# esp.net
KiCad netlist of a schematic drawn in EAGLE
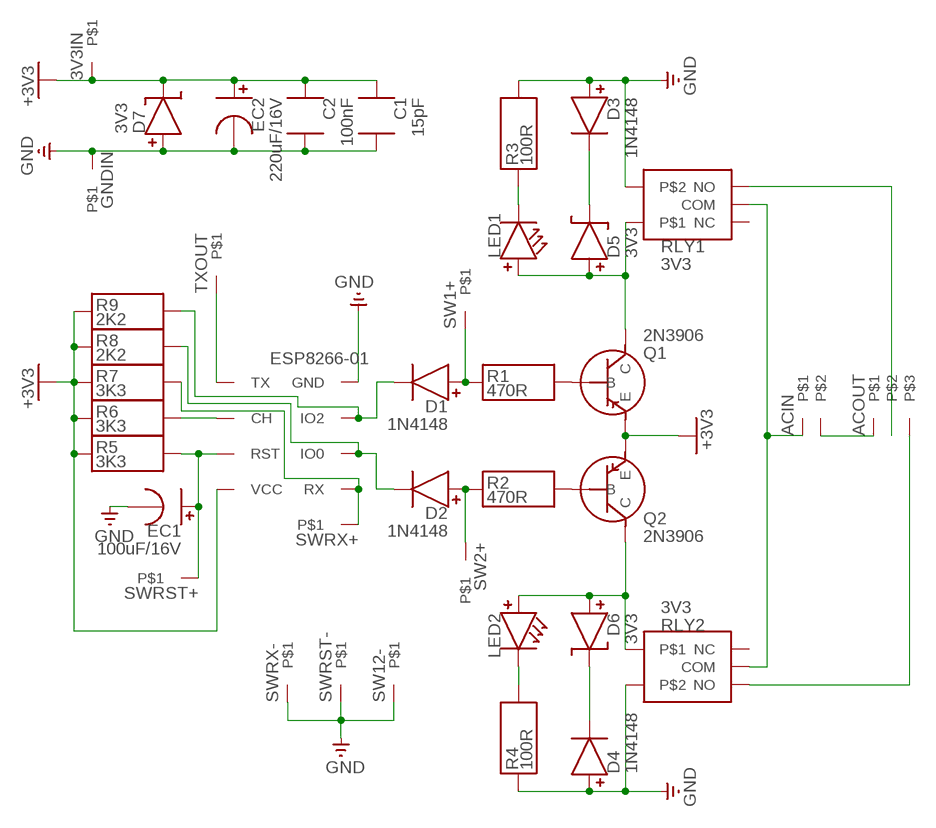
[diagram p0: schematic, sheet 1]

(export (version "E")
  (design (tool "Eeschema 10.0.6"))
  (components
    (comp (ref "3V3IN")
      (value "CON1PINPLUG1")
      (footprint "eagle-import:PINPLUG1")
      (libsource (lib "eagle-import") (part "CON1PINPLUG1"))
    )
    (comp (ref "ACIN")
      (value "CON2CON5.0S2T")
      (footprint "eagle-import:CON5.0S2T")
      (libsource (lib "eagle-import") (part "CON2CON5.0S2T"))
    )
    (comp (ref "ACOUT")
      (value "CON3CON5.0S3T")
      (footprint "eagle-import:CON5.0S3T")
      (libsource (lib "eagle-import") (part "CON3CON5.0S3T"))
    )
    (comp (ref "C1")
      (value "15pF")
      (footprint "eagle-import:CERCAP3.2S")
      (libsource (lib "eagle-import") (part "CAPACITORCERCAP3.2S"))
    )
    (comp (ref "C2")
      (value "100nF")
      (footprint "eagle-import:CERCAP5.6S")
      (libsource (lib "eagle-import") (part "CAPACITORCERCAP5.6S"))
    )
    (comp (ref "D1")
      (value "1N4148")
      (footprint "eagle-import:RD5.0S1.8D")
      (libsource (lib "eagle-import") (part "RECTDIODERD5.0S1.8D"))
    )
    (comp (ref "D2")
      (value "1N4148")
      (footprint "eagle-import:RD5.0S1.8D")
      (libsource (lib "eagle-import") (part "RECTDIODERD5.0S1.8D"))
    )
    (comp (ref "D3")
      (value "1N4148")
      (footprint "eagle-import:RD5.0S1.8D")
      (libsource (lib "eagle-import") (part "RECTDIODERD5.0S1.8D"))
    )
    (comp (ref "D4")
      (value "1N4148")
      (footprint "eagle-import:RD5.0S1.8D")
      (libsource (lib "eagle-import") (part "RECTDIODERD5.0S1.8D"))
    )
    (comp (ref "D5")
      (value "3V3")
      (footprint "eagle-import:ZD6.0S2.0D")
      (libsource (lib "eagle-import") (part "ZENDIODEZD6.0S2.0D"))
    )
    (comp (ref "D6")
      (value "3V3")
      (footprint "eagle-import:ZD6.0S2.0D")
      (libsource (lib "eagle-import") (part "ZENDIODEZD6.0S2.0D"))
    )
    (comp (ref "D7")
      (value "3V3")
      (footprint "eagle-import:ZD6.0S2.0D")
      (libsource (lib "eagle-import") (part "ZENDIODEZD6.0S2.0D"))
    )
    (comp (ref "EC1")
      (value "100uF/16V")
      (footprint "eagle-import:ECAP3.2S5.0D")
      (libsource (lib "eagle-import") (part "ECAPACITORECAP3.2S5.0D"))
    )
    (comp (ref "EC2")
      (value "220uF/16V")
      (footprint "eagle-import:ECAP3.2S5.0D")
      (libsource (lib "eagle-import") (part "ECAPACITORECAP3.2S5.0D"))
    )
    (comp (ref "ESP8266-01")
      (value "ESP8266E01ESP8266E01")
      (footprint "eagle-import:ESP8266E01")
      (libsource (lib "eagle-import") (part "ESP8266E01ESP8266E01"))
    )
    (comp (ref "GNDIN")
      (value "CON1PINPLUG1")
      (footprint "eagle-import:PINPLUG1")
      (libsource (lib "eagle-import") (part "CON1PINPLUG1"))
    )
    (comp (ref "LED1")
      (value "LEDLED3.2S5.0D")
      (footprint "eagle-import:LED3.2S5.0D")
      (libsource (lib "eagle-import") (part "LEDLED3.2S5.0D"))
    )
    (comp (ref "LED2")
      (value "LEDLED3.2S5.0D")
      (footprint "eagle-import:LED3.2S5.0D")
      (libsource (lib "eagle-import") (part "LEDLED3.2S5.0D"))
    )
    (comp (ref "Q1")
      (value "2N3906")
      (footprint "eagle-import:TO92")
      (libsource (lib "eagle-import") (part "BJTPNPTO92"))
    )
    (comp (ref "Q2")
      (value "2N3906")
      (footprint "eagle-import:TO92")
      (libsource (lib "eagle-import") (part "BJTPNPTO92"))
    )
    (comp (ref "R1")
      (value "470R")
      (footprint "eagle-import:HOR.25W")
      (libsource (lib "eagle-import") (part "RESISTORHOR.25W"))
    )
    (comp (ref "R2")
      (value "470R")
      (footprint "eagle-import:HOR.25W")
      (libsource (lib "eagle-import") (part "RESISTORHOR.25W"))
    )
    (comp (ref "R3")
      (value "100R")
      (footprint "eagle-import:HOR.25W")
      (libsource (lib "eagle-import") (part "RESISTORHOR.25W"))
    )
    (comp (ref "R4")
      (value "100R")
      (footprint "eagle-import:HOR.25W")
      (libsource (lib "eagle-import") (part "RESISTORHOR.25W"))
    )
    (comp (ref "R5")
      (value "3K3")
      (footprint "eagle-import:HOR.25W")
      (libsource (lib "eagle-import") (part "RESISTORHOR.25W"))
    )
    (comp (ref "R6")
      (value "3K3")
      (footprint "eagle-import:HOR.25W")
      (libsource (lib "eagle-import") (part "RESISTORHOR.25W"))
    )
    (comp (ref "R7")
      (value "3K3")
      (footprint "eagle-import:HOR.25W")
      (libsource (lib "eagle-import") (part "RESISTORHOR.25W"))
    )
    (comp (ref "R8")
      (value "2K2")
      (footprint "eagle-import:HOR.25W")
      (libsource (lib "eagle-import") (part "RESISTORHOR.25W"))
    )
    (comp (ref "R9")
      (value "2K2")
      (footprint "eagle-import:HOR.25W")
      (libsource (lib "eagle-import") (part "RESISTORHOR.25W"))
    )
    (comp (ref "RLY1")
      (value "3V3")
      (footprint "eagle-import:RLY15W19L")
      (libsource (lib "eagle-import") (part "RELAY5RLY15W19L"))
    )
    (comp (ref "RLY2")
      (value "3V3")
      (footprint "eagle-import:RLY15W19L")
      (libsource (lib "eagle-import") (part "RELAY5RLY15W19L"))
    )
    (comp (ref "SW1+")
      (value "CON1PINPLUG1")
      (footprint "eagle-import:PINPLUG1")
      (libsource (lib "eagle-import") (part "CON1PINPLUG1"))
    )
    (comp (ref "SW2+")
      (value "CON1PINPLUG1")
      (footprint "eagle-import:PINPLUG1")
      (libsource (lib "eagle-import") (part "CON1PINPLUG1"))
    )
    (comp (ref "SW12-")
      (value "CON1PINPLUG1")
      (footprint "eagle-import:PINPLUG1")
      (libsource (lib "eagle-import") (part "CON1PINPLUG1"))
    )
    (comp (ref "SWRST+")
      (value "CON1PINPLUG1")
      (footprint "eagle-import:PINPLUG1")
      (libsource (lib "eagle-import") (part "CON1PINPLUG1"))
    )
    (comp (ref "SWRST-")
      (value "CON1PINPLUG1")
      (footprint "eagle-import:PINPLUG1")
      (libsource (lib "eagle-import") (part "CON1PINPLUG1"))
    )
    (comp (ref "SWRX+")
      (value "CON1PINPLUG1")
      (footprint "eagle-import:PINPLUG1")
      (libsource (lib "eagle-import") (part "CON1PINPLUG1"))
    )
    (comp (ref "SWRX-")
      (value "CON1PINPLUG1")
      (footprint "eagle-import:PINPLUG1")
      (libsource (lib "eagle-import") (part "CON1PINPLUG1"))
    )
    (comp (ref "TXOUT")
      (value "CON1PINPLUG1")
      (footprint "eagle-import:PINPLUG1")
      (libsource (lib "eagle-import") (part "CON1PINPLUG1"))
    )
  )
  (nets
    (net (code "1") (name "+3V3") (class "Default")
      (node (ref "3V3IN") (pin "P$1") (pinfunction "P$1_P$1") (pintype "bidirectional"))
      (node (ref "C1") (pin "P$1") (pinfunction "P$1_P$1") (pintype "passive"))
      (node (ref "C2") (pin "P$1") (pinfunction "P$1_P$1") (pintype "passive"))
      (node (ref "D7") (pin "P-") (pinfunction "P-_P-") (pintype "passive"))
      (node (ref "EC2") (pin "P+") (pinfunction "P+_P+") (pintype "passive"))
      (node (ref "ESP8266-01") (pin "VCC") (pinfunction "VCC_VCC") (pintype "bidirectional"))
      (node (ref "Q1") (pin "3") (pinfunction "E_3") (pintype "bidirectional"))
      (node (ref "Q2") (pin "3") (pinfunction "E_3") (pintype "bidirectional"))
      (node (ref "R5") (pin "P$1") (pinfunction "P$1_P$1") (pintype "passive"))
      (node (ref "R6") (pin "P$1") (pinfunction "P$1_P$1") (pintype "passive"))
      (node (ref "R7") (pin "P$1") (pinfunction "P$1_P$1") (pintype "passive"))
      (node (ref "R8") (pin "P$1") (pinfunction "P$1_P$1") (pintype "passive"))
      (node (ref "R9") (pin "P$1") (pinfunction "P$1_P$1") (pintype "passive"))
    )
    (net (code "2") (name "GND") (class "Default")
      (node (ref "C1") (pin "P$2") (pinfunction "P$2_P$2") (pintype "passive"))
      (node (ref "C2") (pin "P$2") (pinfunction "P$2_P$2") (pintype "passive"))
      (node (ref "D3") (pin "P+") (pinfunction "P+_P+") (pintype "passive"))
      (node (ref "D4") (pin "P+") (pinfunction "P+_P+") (pintype "passive"))
      (node (ref "D7") (pin "P+") (pinfunction "P+_P+") (pintype "passive"))
      (node (ref "EC1") (pin "P-") (pinfunction "P-_P-") (pintype "passive"))
      (node (ref "EC2") (pin "P-") (pinfunction "P-_P-") (pintype "passive"))
      (node (ref "ESP8266-01") (pin "GND") (pinfunction "GND_GND") (pintype "bidirectional"))
      (node (ref "GNDIN") (pin "P$1") (pinfunction "P$1_P$1") (pintype "bidirectional"))
      (node (ref "R3") (pin "P$2") (pinfunction "P$2_P$2") (pintype "passive"))
      (node (ref "R4") (pin "P$1") (pinfunction "P$1_P$1") (pintype "passive"))
      (node (ref "RLY1") (pin "P$2") (pinfunction "P$2_P$2") (pintype "passive"))
      (node (ref "RLY2") (pin "P$2") (pinfunction "P$2_P$2") (pintype "passive"))
      (node (ref "SW12-") (pin "P$1") (pinfunction "P$1_P$1") (pintype "bidirectional"))
      (node (ref "SWRST-") (pin "P$1") (pinfunction "P$1_P$1") (pintype "bidirectional"))
      (node (ref "SWRX-") (pin "P$1") (pinfunction "P$1_P$1") (pintype "bidirectional"))
    )
    (net (code "3") (name "Net-(ACIN-PadP$1)") (class "Default")
      (node (ref "ACIN") (pin "P$1") (pinfunction "P$1_P$1") (pintype "bidirectional"))
      (node (ref "RLY1") (pin "COM") (pinfunction "COM_COM") (pintype "bidirectional"))
      (node (ref "RLY2") (pin "COM") (pinfunction "COM_COM") (pintype "bidirectional"))
    )
    (net (code "4") (name "Net-(ACIN-PadP$2)") (class "Default")
      (node (ref "ACIN") (pin "P$2") (pinfunction "P$2_P$2") (pintype "bidirectional"))
      (node (ref "ACOUT") (pin "P$1") (pinfunction "P$1_P$1") (pintype "bidirectional"))
    )
    (net (code "5") (name "Net-(ACOUT-PadP$2)") (class "Default")
      (node (ref "ACOUT") (pin "P$2") (pinfunction "P$2_P$2") (pintype "bidirectional"))
      (node (ref "RLY1") (pin "NO") (pinfunction "NO_NO") (pintype "bidirectional"))
    )
    (net (code "6") (name "Net-(ACOUT-PadP$3)") (class "Default")
      (node (ref "ACOUT") (pin "P$3") (pinfunction "P$3_P$3") (pintype "bidirectional"))
      (node (ref "RLY2") (pin "NO") (pinfunction "NO_NO") (pintype "bidirectional"))
    )
    (net (code "7") (name "Net-(D1-PadP+)") (class "Default")
      (node (ref "D1") (pin "P+") (pinfunction "P+_P+") (pintype "passive"))
      (node (ref "R1") (pin "P$1") (pinfunction "P$1_P$1") (pintype "passive"))
      (node (ref "SW1+") (pin "P$1") (pinfunction "P$1_P$1") (pintype "bidirectional"))
    )
    (net (code "8") (name "Net-(D1-PadP-)") (class "Default")
      (node (ref "D1") (pin "P-") (pinfunction "P-_P-") (pintype "passive"))
      (node (ref "ESP8266-01") (pin "IO2") (pinfunction "IO2_IO2") (pintype "bidirectional"))
      (node (ref "R9") (pin "P$2") (pinfunction "P$2_P$2") (pintype "passive"))
    )
    (net (code "9") (name "Net-(D2-PadP+)") (class "Default")
      (node (ref "D2") (pin "P+") (pinfunction "P+_P+") (pintype "passive"))
      (node (ref "R2") (pin "P$1") (pinfunction "P$1_P$1") (pintype "passive"))
      (node (ref "SW2+") (pin "P$1") (pinfunction "P$1_P$1") (pintype "bidirectional"))
    )
    (net (code "10") (name "Net-(D2-PadP-)") (class "Default")
      (node (ref "D2") (pin "P-") (pinfunction "P-_P-") (pintype "passive"))
      (node (ref "ESP8266-01") (pin "IO0") (pinfunction "IO0_IO0") (pintype "bidirectional"))
      (node (ref "R8") (pin "P$2") (pinfunction "P$2_P$2") (pintype "passive"))
    )
    (net (code "11") (name "Net-(D3-PadP-)") (class "Default")
      (node (ref "D3") (pin "P-") (pinfunction "P-_P-") (pintype "passive"))
      (node (ref "D5") (pin "P-") (pinfunction "P-_P-") (pintype "passive"))
    )
    (net (code "12") (name "Net-(D4-PadP-)") (class "Default")
      (node (ref "D4") (pin "P-") (pinfunction "P-_P-") (pintype "passive"))
      (node (ref "D6") (pin "P-") (pinfunction "P-_P-") (pintype "passive"))
    )
    (net (code "13") (name "Net-(EC1-PadP+)") (class "Default")
      (node (ref "EC1") (pin "P+") (pinfunction "P+_P+") (pintype "passive"))
      (node (ref "ESP8266-01") (pin "RST") (pinfunction "RST_RST") (pintype "bidirectional"))
      (node (ref "R5") (pin "P$2") (pinfunction "P$2_P$2") (pintype "passive"))
      (node (ref "SWRST+") (pin "P$1") (pinfunction "P$1_P$1") (pintype "bidirectional"))
    )
    (net (code "14") (name "Net-(ESP8266-01-PadCH)") (class "Default")
      (node (ref "ESP8266-01") (pin "CH") (pinfunction "CH_CH") (pintype "bidirectional"))
      (node (ref "R6") (pin "P$2") (pinfunction "P$2_P$2") (pintype "passive"))
    )
    (net (code "15") (name "Net-(ESP8266-01-PadRX)") (class "Default")
      (node (ref "ESP8266-01") (pin "RX") (pinfunction "RX_RX") (pintype "bidirectional"))
      (node (ref "R7") (pin "P$2") (pinfunction "P$2_P$2") (pintype "passive"))
      (node (ref "SWRX+") (pin "P$1") (pinfunction "P$1_P$1") (pintype "bidirectional"))
    )
    (net (code "16") (name "Net-(ESP8266-01-PadTX)") (class "Default")
      (node (ref "ESP8266-01") (pin "TX") (pinfunction "TX_TX") (pintype "bidirectional"))
      (node (ref "TXOUT") (pin "P$1") (pinfunction "P$1_P$1") (pintype "bidirectional"))
    )
    (net (code "17") (name "Net-(LED1-PadP-)") (class "Default")
      (node (ref "LED1") (pin "P-") (pinfunction "P-_P-") (pintype "passive"))
      (node (ref "R3") (pin "P$1") (pinfunction "P$1_P$1") (pintype "passive"))
    )
    (net (code "18") (name "Net-(LED2-PadP-)") (class "Default")
      (node (ref "LED2") (pin "P-") (pinfunction "P-_P-") (pintype "passive"))
      (node (ref "R4") (pin "P$2") (pinfunction "P$2_P$2") (pintype "passive"))
    )
    (net (code "19") (name "Net-(Q1-B)") (class "Default")
      (node (ref "Q1") (pin "2") (pinfunction "B_2") (pintype "bidirectional"))
      (node (ref "R1") (pin "P$2") (pinfunction "P$2_P$2") (pintype "passive"))
    )
    (net (code "20") (name "Net-(Q1-C)") (class "Default")
      (node (ref "D5") (pin "P+") (pinfunction "P+_P+") (pintype "passive"))
      (node (ref "LED1") (pin "P+") (pinfunction "P+_P+") (pintype "passive"))
      (node (ref "Q1") (pin "1") (pinfunction "C_1") (pintype "bidirectional"))
      (node (ref "RLY1") (pin "P$1") (pinfunction "P$1_P$1") (pintype "passive"))
    )
    (net (code "21") (name "Net-(Q2-B)") (class "Default")
      (node (ref "Q2") (pin "2") (pinfunction "B_2") (pintype "bidirectional"))
      (node (ref "R2") (pin "P$2") (pinfunction "P$2_P$2") (pintype "passive"))
    )
    (net (code "22") (name "Net-(Q2-C)") (class "Default")
      (node (ref "D6") (pin "P+") (pinfunction "P+_P+") (pintype "passive"))
      (node (ref "LED2") (pin "P+") (pinfunction "P+_P+") (pintype "passive"))
      (node (ref "Q2") (pin "1") (pinfunction "C_1") (pintype "bidirectional"))
      (node (ref "RLY2") (pin "P$1") (pinfunction "P$1_P$1") (pintype "passive"))
    )
    (net (code "23") (name "unconnected-(RLY1-PadNC)") (class "Default")
      (node (ref "RLY1") (pin "NC") (pinfunction "NC_NC") (pintype "bidirectional"))
    )
    (net (code "24") (name "unconnected-(RLY2-PadNC)") (class "Default")
      (node (ref "RLY2") (pin "NC") (pinfunction "NC_NC") (pintype "bidirectional"))
    )
  )
)
